# mcu.net
KiCad netlist of a schematic drawn in Altium Designer
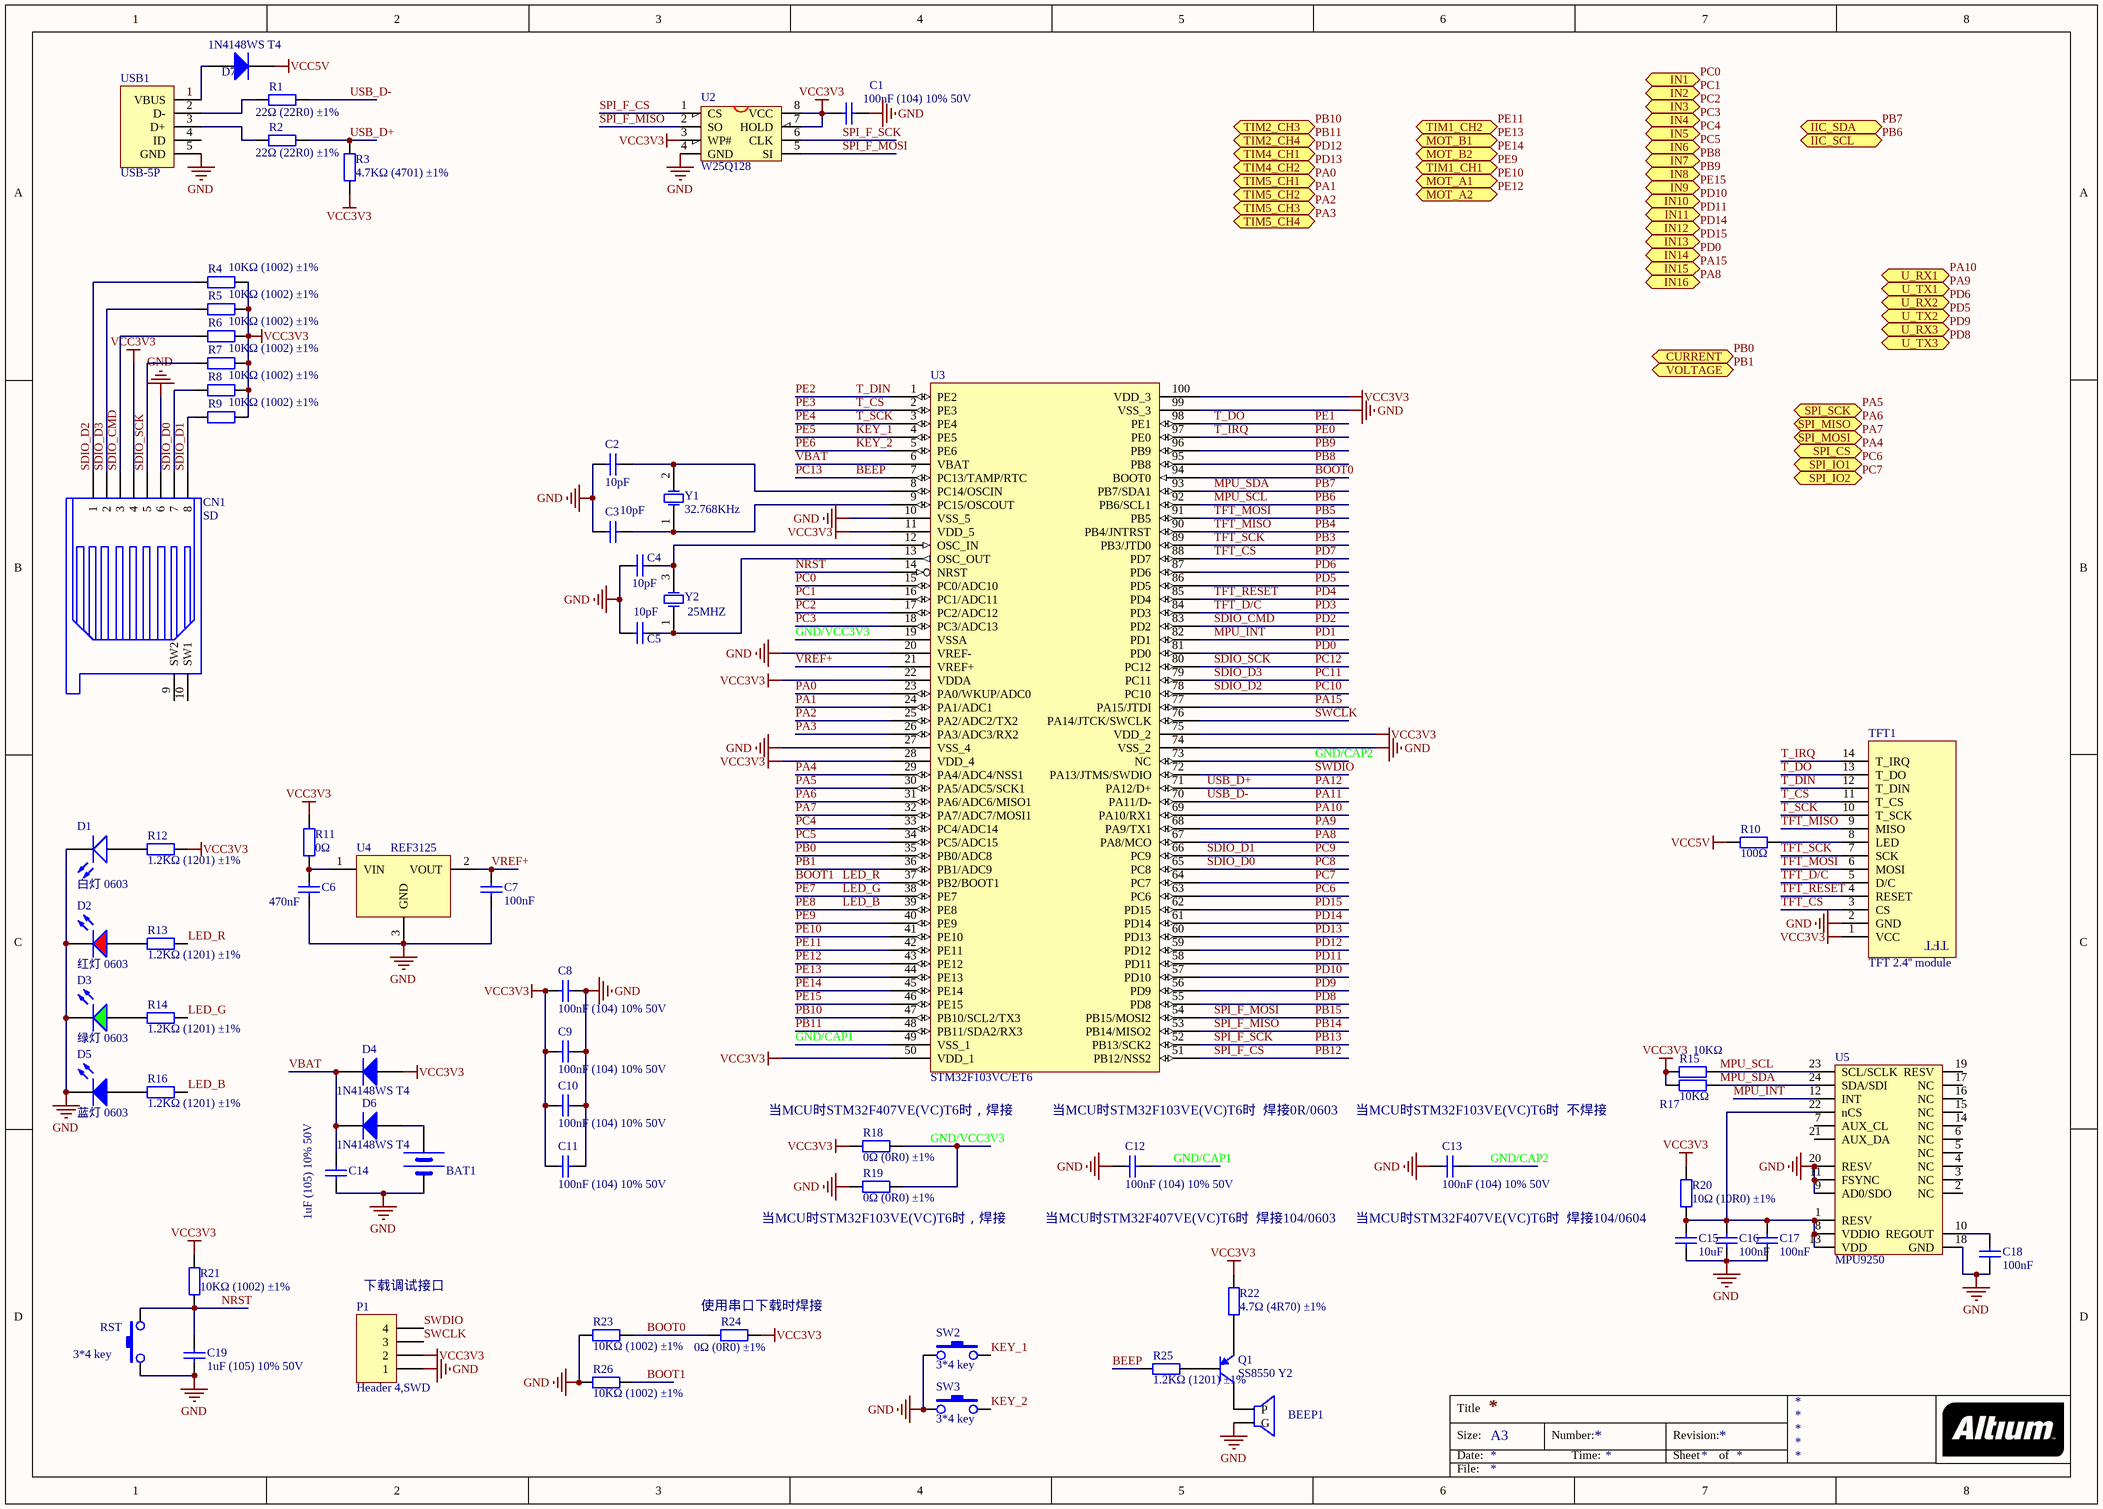
[diagram p0: mcu.SchDoc]

(export (version "E")
  (design (tool "Eeschema 10.0.6"))
  (components
    (comp (ref "BAT1") (value "BATT") (footprint "BATM") (libsource (lib "EXPLORER") (part "BAT")))
    (comp (ref "BEEP1") (value "BEEP") (footprint "BELL-5") (libsource (lib "EXPLORER") (part "BEEP")))
    (comp (ref "C1")
      (value "100nF (104) 10% 50V")
      (footprint "0603_C")
      (description "贴片电容")
      (libsource (lib "Cap") (part "0603 100nF (104) 10% 50V"))
    )
    (comp (ref "C2")
      (value "10pF")
      (footprint "0603_C")
      (description "贴片电容")
      (libsource (lib "Cap") (part "0603 10pF (100) 5% 50V"))
    )
    (comp (ref "C3")
      (value "10pF")
      (footprint "0603_C")
      (description "贴片电容")
      (libsource (lib "Cap") (part "0603 10pF (100) 5% 50V"))
    )
    (comp (ref "C4")
      (value "10pF")
      (footprint "0603_C")
      (description "贴片电容")
      (libsource (lib "Cap") (part "0603 10pF (100) 5% 50V"))
    )
    (comp (ref "C5")
      (value "10pF")
      (footprint "0603_C")
      (description "贴片电容")
      (libsource (lib "Cap") (part "0603 10pF (100) 5% 50V"))
    )
    (comp (ref "C6")
      (value "470nF")
      (footprint "0603_C")
      (description "贴片电容")
      (libsource (lib "Cap") (part "0603 470nF (474) 10% 25V"))
    )
    (comp (ref "C7")
      (value "100nF")
      (footprint "0603_C")
      (description "贴片电容")
      (libsource (lib "Cap") (part "0603 100nF (104) 10% 50V"))
    )
    (comp (ref "C8")
      (value "100nF (104) 10% 50V")
      (footprint "0603_C")
      (description "贴片电容")
      (libsource (lib "Cap") (part "0603 100nF (104) 10% 50V"))
    )
    (comp (ref "C9")
      (value "100nF (104) 10% 50V")
      (footprint "0603_C")
      (description "贴片电容")
      (libsource (lib "Cap") (part "0603 100nF (104) 10% 50V"))
    )
    (comp (ref "C10")
      (value "100nF (104) 10% 50V")
      (footprint "0603_C")
      (description "贴片电容")
      (libsource (lib "Cap") (part "0603 100nF (104) 10% 50V"))
    )
    (comp (ref "C11")
      (value "100nF (104) 10% 50V")
      (footprint "0603_C")
      (description "贴片电容")
      (libsource (lib "Cap") (part "0603 100nF (104) 10% 50V"))
    )
    (comp (ref "C12")
      (value "100nF (104) 10% 50V")
      (footprint "0603_C")
      (description "贴片电容")
      (libsource (lib "Cap") (part "0603 100nF (104) 10% 50V"))
    )
    (comp (ref "C13")
      (value "100nF (104) 10% 50V")
      (footprint "0603_C")
      (description "贴片电容")
      (libsource (lib "Cap") (part "0603 100nF (104) 10% 50V"))
    )
    (comp (ref "C14")
      (value "1uF (105) 10% 50V")
      (footprint "0603_C")
      (description "贴片电容")
      (libsource (lib "Cap") (part "0603 1uF (105) 10% 50V"))
    )
    (comp (ref "C15")
      (value "10uF")
      (footprint "0603_C")
      (description "贴片电容")
      (libsource (lib "Cap") (part "0603 10uF (106) 10% 10V"))
    )
    (comp (ref "C16")
      (value "100nF")
      (footprint "0603_C")
      (description "贴片电容")
      (libsource (lib "Cap") (part "0603 100nF (104) 10% 50V"))
    )
    (comp (ref "C17")
      (value "100nF")
      (footprint "0603_C")
      (description "贴片电容")
      (libsource (lib "Cap") (part "0603 100nF (104) 10% 50V"))
    )
    (comp (ref "C18")
      (value "100nF")
      (footprint "0603_C")
      (description "贴片电容")
      (libsource (lib "Cap") (part "0603 100nF (104) 10% 50V"))
    )
    (comp (ref "C19")
      (value "1uF (105) 10% 50V")
      (footprint "0603_C")
      (description "贴片电容")
      (libsource (lib "Cap") (part "0603 1uF (105) 10% 50V"))
    )
    (comp (ref "CN1")
      (value "SD")
      (footprint "TF")
      (libsource (lib "STM32F407VET6mini最小系统-原理图库") (part "SMS016AFA5E"))
    )
    (comp (ref "D1")
      (value "白灯 0603")
      (footprint "0603_LED_S1")
      (description "发光二极管")
      (libsource (lib "LED") (part "0603 白灯"))
    )
    (comp (ref "D2")
      (value "红灯 0603")
      (footprint "0603_LED_S1")
      (description "发光二极管")
      (libsource (lib "LED") (part "0603 红灯"))
    )
    (comp (ref "D3")
      (value "绿灯 0603")
      (footprint "0603_LED_S1")
      (description "发光二极管")
      (libsource (lib "LED") (part "0603 绿灯"))
    )
    (comp (ref "D4")
      (value "1N4148WS T4")
      (footprint "SOD-323")
      (description "二极管")
      (libsource (lib "Diode") (part "SOD-323 1N4148WS T4"))
    )
    (comp (ref "D5")
      (value "蓝灯 0603")
      (footprint "0603_LED_S1")
      (description "发光二极管")
      (libsource (lib "LED") (part "0603 蓝灯"))
    )
    (comp (ref "D6")
      (value "1N4148WS T4")
      (footprint "SOD-323")
      (description "二极管")
      (libsource (lib "Diode") (part "SOD-323 1N4148WS T4"))
    )
    (comp (ref "D7")
      (value "1N4148WS T4")
      (footprint "SOD-323")
      (description "二极管")
      (libsource (lib "Diode") (part "SOD-323 1N4148WS T4"))
    )
    (comp (ref "P1")
      (value "Header 4,SWD")
      (footprint "HDR1X4")
      (description "Header, 4-Pin")
      (fields (field (name "PUBLISHER") "Altium Limited"))
      (libsource (lib "Miscellaneous Connectors") (part "Header 4"))
    )
    (comp (ref "Q1")
      (value "SS8550 Y2")
      (footprint "SOT-23(SOT-23-3)")
      (description "三极管")
      (libsource (lib "Transistor_PNP") (part "SOT-23 SS8550 Y2"))
    )
    (comp (ref "R1")
      (value "22Ω (22R0) ±1%")
      (footprint "0603_R")
      (description "贴片电阻")
      (libsource (lib "RES") (part "0603 22Ω (22R0) 1%"))
    )
    (comp (ref "R2")
      (value "22Ω (22R0) ±1%")
      (footprint "0603_R")
      (description "贴片电阻")
      (libsource (lib "RES") (part "0603 22Ω (22R0) 1%"))
    )
    (comp (ref "R3")
      (value "4.7KΩ (4701) ±1%")
      (footprint "0603_R")
      (description "贴片电阻")
      (libsource (lib "RES") (part "0603 4.7KΩ (4701) 1%"))
    )
    (comp (ref "R4")
      (value "10KΩ (1002) ±1%")
      (footprint "0603_R")
      (description "贴片电阻")
      (libsource (lib "RES") (part "0603 10KΩ (1002) 1%"))
    )
    (comp (ref "R5")
      (value "10KΩ (1002) ±1%")
      (footprint "0603_R")
      (description "贴片电阻")
      (libsource (lib "RES") (part "0603 10KΩ (1002) 1%"))
    )
    (comp (ref "R6")
      (value "10KΩ (1002) ±1%")
      (footprint "0603_R")
      (description "贴片电阻")
      (libsource (lib "RES") (part "0603 10KΩ (1002) 1%"))
    )
    (comp (ref "R7")
      (value "10KΩ (1002) ±1%")
      (footprint "0603_R")
      (description "贴片电阻")
      (libsource (lib "RES") (part "0603 10KΩ (1002) 1%"))
    )
    (comp (ref "R8")
      (value "10KΩ (1002) ±1%")
      (footprint "0603_R")
      (description "贴片电阻")
      (libsource (lib "RES") (part "0603 10KΩ (1002) 1%"))
    )
    (comp (ref "R9")
      (value "10KΩ (1002) ±1%")
      (footprint "0603_R")
      (description "贴片电阻")
      (libsource (lib "RES") (part "0603 10KΩ (1002) 1%"))
    )
    (comp (ref "R10")
      (value "100Ω")
      (footprint "0603_R")
      (description "贴片电阻")
      (libsource (lib "RES") (part "0603 100Ω (1000) 1%"))
    )
    (comp (ref "R11")
      (value "0Ω")
      (footprint "0603_R")
      (description "贴片电阻")
      (libsource (lib "") (part "0603 0Ω (0R0) 1%_1"))
    )
    (comp (ref "R12")
      (value "1.2KΩ (1201) ±1%")
      (footprint "0603_R")
      (description "贴片电阻")
      (libsource (lib "RES") (part "0603 1.2KΩ (1201) 1%"))
    )
    (comp (ref "R13")
      (value "1.2KΩ (1201) ±1%")
      (footprint "0603_R")
      (description "贴片电阻")
      (libsource (lib "RES") (part "0603 1.2KΩ (1201) 1%"))
    )
    (comp (ref "R14")
      (value "1.2KΩ (1201) ±1%")
      (footprint "0603_R")
      (description "贴片电阻")
      (libsource (lib "RES") (part "0603 1.2KΩ (1201) 1%"))
    )
    (comp (ref "R15")
      (value "10KΩ")
      (footprint "0603_R")
      (description "贴片电阻")
      (libsource (lib "") (part "0603 10KΩ (1002) 1%_2"))
    )
    (comp (ref "R16")
      (value "1.2KΩ (1201) ±1%")
      (footprint "0603_R")
      (description "贴片电阻")
      (libsource (lib "RES") (part "0603 1.2KΩ (1201) 1%"))
    )
    (comp (ref "R17")
      (value "10KΩ")
      (footprint "0603_R")
      (description "贴片电阻")
      (libsource (lib "") (part "0603 10KΩ (1002) 1%_2"))
    )
    (comp (ref "R18")
      (value "0Ω (0R0) ±1%")
      (footprint "0603_R")
      (description "贴片电阻")
      (libsource (lib "RES") (part "0603 0Ω (0R0) 1%"))
    )
    (comp (ref "R19")
      (value "0Ω (0R0) ±1%")
      (footprint "0603_R")
      (description "贴片电阻")
      (libsource (lib "RES") (part "0603 0Ω (0R0) 1%"))
    )
    (comp (ref "R20")
      (value "10Ω (10R0) ±1%")
      (footprint "0603_R")
      (description "贴片电阻")
      (libsource (lib "RES") (part "0603 10Ω (10R0) 1%"))
    )
    (comp (ref "R21")
      (value "10KΩ (1002) ±1%")
      (footprint "0603_R")
      (description "贴片电阻")
      (libsource (lib "") (part "0603 10KΩ (1002) 1%_1"))
    )
    (comp (ref "R22")
      (value "4.7Ω (4R70) ±1%")
      (footprint "0603_R")
      (description "贴片电阻")
      (libsource (lib "RES") (part "0603 4.7Ω (4R70) 1%"))
    )
    (comp (ref "R23")
      (value "10KΩ (1002) ±1%")
      (footprint "0603_R")
      (description "贴片电阻")
      (libsource (lib "RES") (part "0603 10KΩ (1002) 1%"))
    )
    (comp (ref "R24")
      (value "0Ω (0R0) ±1%")
      (footprint "0603_R")
      (description "贴片电阻")
      (libsource (lib "RES") (part "0603 0Ω (0R0) 1%"))
    )
    (comp (ref "R25")
      (value "1.2KΩ (1201) ±1%")
      (footprint "0603_R")
      (description "贴片电阻")
      (libsource (lib "RES") (part "0603 1.2KΩ (1201) 1%"))
    )
    (comp (ref "R26")
      (value "10KΩ (1002) ±1%")
      (footprint "0603_R")
      (description "贴片电阻")
      (libsource (lib "RES") (part "0603 10KΩ (1002) 1%"))
    )
    (comp (ref "RST")
      (value "3*4 key")
      (footprint "KEY-SMT")
      (description "SWITCH")
      (libsource (lib "STM32F407VET6mini最小系统-原理图库") (part "SW-PB_V"))
    )
    (comp (ref "SW2")
      (value "3*4 key")
      (footprint "KEY-SMT")
      (description "SWITCH")
      (libsource (lib "STM32F407VET6mini最小系统-原理图库") (part "SW-PB_V"))
    )
    (comp (ref "SW3")
      (value "3*4 key")
      (footprint "KEY-SMT")
      (description "SWITCH")
      (libsource (lib "STM32F407VET6mini最小系统-原理图库") (part "SW-PB_V"))
    )
    (comp (ref "TFT1")
      (value "TFT 2.4'' module")
      (footprint "TFT 2.4'' module")
      (libsource (lib "MySchlib") (part "TFT 2.4'' module"))
    )
    (comp (ref "U2")
      (value "W25Q128")
      (footprint "SOIC-8")
      (description "W25X16;SST25VF016;MX25L1605")
      (libsource (lib "EXPLORER") (part "W25X16"))
    )
    (comp (ref "U3")
      (value "STM32F103VC/ET6")
      (footprint "LQFP-100")
      (libsource (lib "STM32F407VET6mini最小系统-原理图库") (part "STM32F103VBH6"))
    )
    (comp (ref "U4")
      (value "REF3125")
      (footprint "SOT-23(SOT-23-3)")
      (description "电压基准芯片")
      (libsource (lib "*") (part "REF3125"))
    )
    (comp (ref "U5")
      (value "MPU9250")
      (footprint "QFN24-t")
      (description "9轴运动处理传感器")
      (libsource (lib "STM32F429_F746") (part "MPU9250"))
    )
    (comp (ref "USB1")
      (value "USB-5P")
      (footprint "USB-MICRO_B")
      (description "微型USB母座")
      (libsource (lib "*") (part "USB-5P"))
    )
    (comp (ref "Y1")
      (value "32.768KHz")
      (footprint "MC-306")
      (description "Crystal Oscillator")
      (fields (field (name "PUBLISHER") "Altium Limited"))
      (libsource (lib "STM32F407VET6mini最小系统-原理图库") (part "XTAL"))
    )
    (comp (ref "Y2")
      (value "25MHZ")
      (footprint "SMD-3225_4P")
      (description "贴片晶振")
      (libsource (lib "CrystalOscillator") (part "SMD-3225_4P  25MHZ 12PF 10PPM"))
    )
  )
  (nets
    (net (code "1") (name "/BEEP") (class "Default")
      (node (ref "R25") (pin "1") (pinfunction "1_1") (pintype "passive"))
      (node (ref "U3") (pin "7") (pinfunction "PC13/TAMP/RTC_7") (pintype "bidirectional"))
    )
    (net (code "2") (name "/BOOT0") (class "Default")
      (node (ref "R23") (pin "1") (pinfunction "1_1") (pintype "passive"))
      (node (ref "R24") (pin "1") (pinfunction "1_1") (pintype "passive"))
      (node (ref "U3") (pin "94") (pinfunction "BOOT0_94") (pintype "input"))
    )
    (net (code "3") (name "/BOOT1") (class "Default")
      (node (ref "R13") (pin "2") (pinfunction "2_2") (pintype "passive"))
      (node (ref "R26") (pin "1") (pinfunction "1_1") (pintype "passive"))
      (node (ref "U3") (pin "37") (pinfunction "PB2/BOOT1_37") (pintype "bidirectional"))
    )
    (net (code "4") (name "/GND{slash}CAP1") (class "Default")
      (node (ref "C12") (pin "2") (pinfunction "2_2") (pintype "passive"))
      (node (ref "U3") (pin "49") (pinfunction "VSS_1_49") (pintype "power_in"))
    )
    (net (code "5") (name "/GND{slash}CAP2") (class "Default")
      (node (ref "C13") (pin "2") (pinfunction "2_2") (pintype "passive"))
      (node (ref "U3") (pin "73") (pinfunction "NC_73") (pintype "bidirectional"))
    )
    (net (code "6") (name "/GND{slash}VCC3V3") (class "Default")
      (node (ref "R18") (pin "2") (pinfunction "2_2") (pintype "passive"))
      (node (ref "R19") (pin "2") (pinfunction "2_2") (pintype "passive"))
      (node (ref "U3") (pin "19") (pinfunction "VSSA_19") (pintype "power_in"))
    )
    (net (code "7") (name "/KEY_1") (class "Default")
      (node (ref "SW2") (pin "2") (pinfunction "2_2") (pintype "passive"))
      (node (ref "U3") (pin "4") (pinfunction "PE5_4") (pintype "bidirectional"))
    )
    (net (code "8") (name "/KEY_2") (class "Default")
      (node (ref "SW3") (pin "2") (pinfunction "2_2") (pintype "passive"))
      (node (ref "U3") (pin "5") (pinfunction "PE6_5") (pintype "bidirectional"))
    )
    (net (code "9") (name "/LED_B") (class "Default")
      (node (ref "R16") (pin "2") (pinfunction "2_2") (pintype "passive"))
      (node (ref "U3") (pin "39") (pinfunction "PE8_39") (pintype "bidirectional"))
    )
    (net (code "10") (name "/LED_G") (class "Default")
      (node (ref "R14") (pin "2") (pinfunction "2_2") (pintype "passive"))
      (node (ref "U3") (pin "38") (pinfunction "PE7_38") (pintype "bidirectional"))
    )
    (net (code "11") (name "/MPU_INT") (class "Default")
      (node (ref "U3") (pin "82") (pinfunction "PD1_82") (pintype "bidirectional"))
      (node (ref "U5") (pin "12") (pinfunction "INT_12") (pintype "passive"))
    )
    (net (code "12") (name "/MPU_SCL") (class "Default")
      (node (ref "R15") (pin "2") (pinfunction "2_2") (pintype "passive"))
      (node (ref "U3") (pin "92") (pinfunction "PB6/SCL1_92") (pintype "bidirectional"))
      (node (ref "U5") (pin "23") (pinfunction "SCL/SCLK_23") (pintype "passive"))
    )
    (net (code "13") (name "/MPU_SDA") (class "Default")
      (node (ref "R17") (pin "2") (pinfunction "2_2") (pintype "passive"))
      (node (ref "U3") (pin "93") (pinfunction "PB7/SDA1_93") (pintype "bidirectional"))
      (node (ref "U5") (pin "24") (pinfunction "SDA/SDI_24") (pintype "passive"))
    )
    (net (code "14") (name "/NRST") (class "Default")
      (node (ref "C19") (pin "2") (pinfunction "2_2") (pintype "passive"))
      (node (ref "R21") (pin "1") (pinfunction "1_1") (pintype "passive"))
      (node (ref "RST") (pin "2") (pinfunction "2_2") (pintype "passive"))
      (node (ref "U3") (pin "14") (pinfunction "NRST_14") (pintype "input"))
    )
    (net (code "15") (name "/PA0") (class "Default")
      (node (ref "U3") (pin "23") (pinfunction "PA0/WKUP/ADC0_23") (pintype "bidirectional"))
    )
    (net (code "16") (name "/PA1") (class "Default")
      (node (ref "U3") (pin "24") (pinfunction "PA1/ADC1_24") (pintype "bidirectional"))
    )
    (net (code "17") (name "/PA2") (class "Default")
      (node (ref "U3") (pin "25") (pinfunction "PA2/ADC2/TX2_25") (pintype "bidirectional"))
    )
    (net (code "18") (name "/PA3") (class "Default")
      (node (ref "U3") (pin "26") (pinfunction "PA3/ADC3/RX2_26") (pintype "bidirectional"))
    )
    (net (code "19") (name "/PA4") (class "Default")
      (node (ref "U3") (pin "29") (pinfunction "PA4/ADC4/NSS1_29") (pintype "bidirectional"))
    )
    (net (code "20") (name "/PA5") (class "Default")
      (node (ref "U3") (pin "30") (pinfunction "PA5/ADC5/SCK1_30") (pintype "bidirectional"))
    )
    (net (code "21") (name "/PA6") (class "Default")
      (node (ref "U3") (pin "31") (pinfunction "PA6/ADC6/MISO1_31") (pintype "bidirectional"))
    )
    (net (code "22") (name "/PA7") (class "Default")
      (node (ref "U3") (pin "32") (pinfunction "PA7/ADC7/MOSI1_32") (pintype "bidirectional"))
    )
    (net (code "23") (name "/PA8") (class "Default")
      (node (ref "U3") (pin "67") (pinfunction "PA8/MCO_67") (pintype "bidirectional"))
    )
    (net (code "24") (name "/PA9") (class "Default")
      (node (ref "U3") (pin "68") (pinfunction "PA9/TX1_68") (pintype "bidirectional"))
    )
    (net (code "25") (name "/PA10") (class "Default")
      (node (ref "U3") (pin "69") (pinfunction "PA10/RX1_69") (pintype "bidirectional"))
    )
    (net (code "26") (name "/PA11") (class "Default")
      (node (ref "R1") (pin "2") (pinfunction "2_2") (pintype "passive"))
      (node (ref "U3") (pin "70") (pinfunction "PA11/D-_70") (pintype "bidirectional"))
    )
    (net (code "27") (name "/PA12") (class "Default")
      (node (ref "R2") (pin "2") (pinfunction "2_2") (pintype "passive"))
      (node (ref "R3") (pin "2") (pinfunction "2_2") (pintype "passive"))
      (node (ref "U3") (pin "71") (pinfunction "PA12/D+_71") (pintype "bidirectional"))
    )
    (net (code "28") (name "/PA15") (class "Default")
      (node (ref "U3") (pin "77") (pinfunction "PA15/JTDI_77") (pintype "bidirectional"))
    )
    (net (code "29") (name "/PB0") (class "Default")
      (node (ref "U3") (pin "35") (pinfunction "PB0/ADC8_35") (pintype "bidirectional"))
    )
    (net (code "30") (name "/PB1") (class "Default")
      (node (ref "U3") (pin "36") (pinfunction "PB1/ADC9_36") (pintype "bidirectional"))
    )
    (net (code "31") (name "/PB3") (class "Default")
      (node (ref "TFT1") (pin "7") (pinfunction "SCK_7") (pintype "passive"))
      (node (ref "U3") (pin "89") (pinfunction "PB3/JTD0_89") (pintype "bidirectional"))
    )
    (net (code "32") (name "/PB4") (class "Default")
      (node (ref "TFT1") (pin "9") (pinfunction "MISO_9") (pintype "passive"))
      (node (ref "U3") (pin "90") (pinfunction "PB4/JNTRST_90") (pintype "bidirectional"))
    )
    (net (code "33") (name "/PB5") (class "Default")
      (node (ref "TFT1") (pin "6") (pinfunction "MOSI_6") (pintype "passive"))
      (node (ref "U3") (pin "91") (pinfunction "PB5_91") (pintype "bidirectional"))
    )
    (net (code "34") (name "/PB8") (class "Default")
      (node (ref "U3") (pin "95") (pinfunction "PB8_95") (pintype "bidirectional"))
    )
    (net (code "35") (name "/PB9") (class "Default")
      (node (ref "U3") (pin "96") (pinfunction "PB9_96") (pintype "bidirectional"))
    )
    (net (code "36") (name "/PB10") (class "Default")
      (node (ref "U3") (pin "47") (pinfunction "PB10/SCL2/TX3_47") (pintype "bidirectional"))
    )
    (net (code "37") (name "/PB11") (class "Default")
      (node (ref "U3") (pin "48") (pinfunction "PB11/SDA2/RX3_48") (pintype "bidirectional"))
    )
    (net (code "38") (name "/PB12") (class "Default")
      (node (ref "U2") (pin "1") (pinfunction "CS_1") (pintype "passive"))
      (node (ref "U3") (pin "51") (pinfunction "PB12/NSS2_51") (pintype "bidirectional"))
    )
    (net (code "39") (name "/PB13") (class "Default")
      (node (ref "U2") (pin "6") (pinfunction "CLK_6") (pintype "passive"))
      (node (ref "U3") (pin "52") (pinfunction "PB13/SCK2_52") (pintype "bidirectional"))
    )
    (net (code "40") (name "/PB14") (class "Default")
      (node (ref "U2") (pin "2") (pinfunction "SO_2") (pintype "passive"))
      (node (ref "U3") (pin "53") (pinfunction "PB14/MISO2_53") (pintype "bidirectional"))
    )
    (net (code "41") (name "/PB15") (class "Default")
      (node (ref "U2") (pin "5") (pinfunction "SI_5") (pintype "passive"))
      (node (ref "U3") (pin "54") (pinfunction "PB15/MOSI2_54") (pintype "bidirectional"))
    )
    (net (code "42") (name "/PC0") (class "Default")
      (node (ref "U3") (pin "15") (pinfunction "PC0/ADC10_15") (pintype "bidirectional"))
    )
    (net (code "43") (name "/PC1") (class "Default")
      (node (ref "U3") (pin "16") (pinfunction "PC1/ADC11_16") (pintype "bidirectional"))
    )
    (net (code "44") (name "/PC2") (class "Default")
      (node (ref "U3") (pin "17") (pinfunction "PC2/ADC12_17") (pintype "bidirectional"))
    )
    (net (code "45") (name "/PC3") (class "Default")
      (node (ref "U3") (pin "18") (pinfunction "PC3/ADC13_18") (pintype "bidirectional"))
    )
    (net (code "46") (name "/PC4") (class "Default")
      (node (ref "U3") (pin "33") (pinfunction "PC4/ADC14_33") (pintype "bidirectional"))
    )
    (net (code "47") (name "/PC5") (class "Default")
      (node (ref "U3") (pin "34") (pinfunction "PC5/ADC15_34") (pintype "bidirectional"))
    )
    (net (code "48") (name "/PC6") (class "Default")
      (node (ref "U3") (pin "63") (pinfunction "PC6_63") (pintype "bidirectional"))
    )
    (net (code "49") (name "/PC7") (class "Default")
      (node (ref "U3") (pin "64") (pinfunction "PC7_64") (pintype "bidirectional"))
    )
    (net (code "50") (name "/PC8") (class "Default")
      (node (ref "CN1") (pin "7") (pinfunction "7_7") (pintype "passive"))
      (node (ref "R8") (pin "2") (pinfunction "2_2") (pintype "passive"))
      (node (ref "U3") (pin "65") (pinfunction "PC8_65") (pintype "bidirectional"))
    )
    (net (code "51") (name "/PC9") (class "Default")
      (node (ref "CN1") (pin "8") (pinfunction "8_8") (pintype "passive"))
      (node (ref "R9") (pin "2") (pinfunction "2_2") (pintype "passive"))
      (node (ref "U3") (pin "66") (pinfunction "PC9_66") (pintype "bidirectional"))
    )
    (net (code "52") (name "/PC10") (class "Default")
      (node (ref "CN1") (pin "1") (pinfunction "1_1") (pintype "passive"))
      (node (ref "R4") (pin "2") (pinfunction "2_2") (pintype "passive"))
      (node (ref "U3") (pin "78") (pinfunction "PC10_78") (pintype "bidirectional"))
    )
    (net (code "53") (name "/PC11") (class "Default")
      (node (ref "CN1") (pin "2") (pinfunction "2_2") (pintype "passive"))
      (node (ref "R5") (pin "2") (pinfunction "2_2") (pintype "passive"))
      (node (ref "U3") (pin "79") (pinfunction "PC11_79") (pintype "bidirectional"))
    )
    (net (code "54") (name "/PC12") (class "Default")
      (node (ref "CN1") (pin "5") (pinfunction "5_5") (pintype "passive"))
      (node (ref "R7") (pin "2") (pinfunction "2_2") (pintype "passive"))
      (node (ref "U3") (pin "80") (pinfunction "PC12_80") (pintype "bidirectional"))
    )
    (net (code "55") (name "/PD0") (class "Default")
      (node (ref "U3") (pin "81") (pinfunction "PD0_81") (pintype "bidirectional"))
    )
    (net (code "56") (name "/PD2") (class "Default")
      (node (ref "CN1") (pin "3") (pinfunction "3_3") (pintype "passive"))
      (node (ref "R6") (pin "2") (pinfunction "2_2") (pintype "passive"))
      (node (ref "U3") (pin "83") (pinfunction "PD2_83") (pintype "bidirectional"))
    )
    (net (code "57") (name "/PD3") (class "Default")
      (node (ref "TFT1") (pin "5") (pinfunction "D/C_5") (pintype "passive"))
      (node (ref "U3") (pin "84") (pinfunction "PD3_84") (pintype "bidirectional"))
    )
    (net (code "58") (name "/PD4") (class "Default")
      (node (ref "TFT1") (pin "4") (pinfunction "RESET_4") (pintype "passive"))
      (node (ref "U3") (pin "85") (pinfunction "PD4_85") (pintype "bidirectional"))
    )
    (net (code "59") (name "/PD5") (class "Default")
      (node (ref "U3") (pin "86") (pinfunction "PD5_86") (pintype "bidirectional"))
    )
    (net (code "60") (name "/PD6") (class "Default")
      (node (ref "U3") (pin "87") (pinfunction "PD6_87") (pintype "bidirectional"))
    )
    (net (code "61") (name "/PD7") (class "Default")
      (node (ref "TFT1") (pin "3") (pinfunction "CS_3") (pintype "passive"))
      (node (ref "U3") (pin "88") (pinfunction "PD7_88") (pintype "bidirectional"))
    )
    (net (code "62") (name "/PD8") (class "Default")
      (node (ref "U3") (pin "55") (pinfunction "PD8_55") (pintype "bidirectional"))
    )
    (net (code "63") (name "/PD9") (class "Default")
      (node (ref "U3") (pin "56") (pinfunction "PD9_56") (pintype "bidirectional"))
    )
    (net (code "64") (name "/PD10") (class "Default")
      (node (ref "U3") (pin "57") (pinfunction "PD10_57") (pintype "bidirectional"))
    )
    (net (code "65") (name "/PD11") (class "Default")
      (node (ref "U3") (pin "58") (pinfunction "PD11_58") (pintype "bidirectional"))
    )
    (net (code "66") (name "/PD12") (class "Default")
      (node (ref "U3") (pin "59") (pinfunction "PD12_59") (pintype "bidirectional"))
    )
    (net (code "67") (name "/PD13") (class "Default")
      (node (ref "U3") (pin "60") (pinfunction "PD13_60") (pintype "bidirectional"))
    )
    (net (code "68") (name "/PD14") (class "Default")
      (node (ref "U3") (pin "61") (pinfunction "PD14_61") (pintype "bidirectional"))
    )
    (net (code "69") (name "/PD15") (class "Default")
      (node (ref "U3") (pin "62") (pinfunction "PD15_62") (pintype "bidirectional"))
    )
    (net (code "70") (name "/PE0") (class "Default")
      (node (ref "TFT1") (pin "14") (pinfunction "T_IRQ_14") (pintype "passive"))
      (node (ref "U3") (pin "97") (pinfunction "PE0_97") (pintype "bidirectional"))
    )
    (net (code "71") (name "/PE1") (class "Default")
      (node (ref "TFT1") (pin "13") (pinfunction "T_DO_13") (pintype "passive"))
      (node (ref "U3") (pin "98") (pinfunction "PE1_98") (pintype "bidirectional"))
    )
    (net (code "72") (name "/PE2") (class "Default")
      (node (ref "TFT1") (pin "12") (pinfunction "T_DIN_12") (pintype "passive"))
      (node (ref "U3") (pin "1") (pinfunction "PE2_1") (pintype "bidirectional"))
    )
    (net (code "73") (name "/PE3") (class "Default")
      (node (ref "TFT1") (pin "11") (pinfunction "T_CS_11") (pintype "passive"))
      (node (ref "U3") (pin "2") (pinfunction "PE3_2") (pintype "bidirectional"))
    )
    (net (code "74") (name "/PE4") (class "Default")
      (node (ref "TFT1") (pin "10") (pinfunction "T_SCK_10") (pintype "passive"))
      (node (ref "U3") (pin "3") (pinfunction "PE4_3") (pintype "bidirectional"))
    )
    (net (code "75") (name "/PE9") (class "Default")
      (node (ref "U3") (pin "40") (pinfunction "PE9_40") (pintype "bidirectional"))
    )
    (net (code "76") (name "/PE10") (class "Default")
      (node (ref "U3") (pin "41") (pinfunction "PE10_41") (pintype "bidirectional"))
    )
    (net (code "77") (name "/PE11") (class "Default")
      (node (ref "U3") (pin "42") (pinfunction "PE11_42") (pintype "bidirectional"))
    )
    (net (code "78") (name "/PE12") (class "Default")
      (node (ref "U3") (pin "43") (pinfunction "PE12_43") (pintype "bidirectional"))
    )
    (net (code "79") (name "/PE13") (class "Default")
      (node (ref "U3") (pin "44") (pinfunction "PE13_44") (pintype "bidirectional"))
    )
    (net (code "80") (name "/PE14") (class "Default")
      (node (ref "U3") (pin "45") (pinfunction "PE14_45") (pintype "bidirectional"))
    )
    (net (code "81") (name "/PE15") (class "Default")
      (node (ref "U3") (pin "46") (pinfunction "PE15_46") (pintype "bidirectional"))
    )
    (net (code "82") (name "/SWCLK") (class "Default")
      (node (ref "P1") (pin "3") (pinfunction "3_3") (pintype "passive"))
      (node (ref "U3") (pin "76") (pinfunction "PA14/JTCK/SWCLK_76") (pintype "bidirectional"))
    )
    (net (code "83") (name "/SWDIO") (class "Default")
      (node (ref "P1") (pin "4") (pinfunction "4_4") (pintype "passive"))
      (node (ref "U3") (pin "72") (pinfunction "PA13/JTMS/SWDIO_72") (pintype "bidirectional"))
    )
    (net (code "84") (name "/VBAT") (class "Default")
      (node (ref "C14") (pin "2") (pinfunction "2_2") (pintype "passive"))
      (node (ref "D4") (pin "2") (pinfunction "K_2") (pintype "passive"))
      (node (ref "D6") (pin "2") (pinfunction "K_2") (pintype "passive"))
      (node (ref "U3") (pin "6") (pinfunction "VBAT_6") (pintype "power_in"))
    )
    (net (code "85") (name "/VREF+") (class "Default")
      (node (ref "C7") (pin "2") (pinfunction "2_2") (pintype "passive"))
      (node (ref "U3") (pin "21") (pinfunction "VREF+_21") (pintype "power_in"))
      (node (ref "U4") (pin "2") (pinfunction "VOUT_2") (pintype "passive"))
    )
    (net (code "86") (name "GND") (class "Default")
      (node (ref "BAT1") (pin "2") (pinfunction "GND_2") (pintype "passive"))
      (node (ref "BEEP1") (pin "2") (pinfunction "G_2") (pintype "passive"))
      (node (ref "C1") (pin "2") (pinfunction "2_2") (pintype "passive"))
      (node (ref "C10") (pin "2") (pinfunction "2_2") (pintype "passive"))
      (node (ref "C11") (pin "2") (pinfunction "2_2") (pintype "passive"))
      (node (ref "C12") (pin "1") (pinfunction "1_1") (pintype "passive"))
      (node (ref "C13") (pin "1") (pinfunction "1_1") (pintype "passive"))
      (node (ref "C14") (pin "1") (pinfunction "1_1") (pintype "passive"))
      (node (ref "C15") (pin "1") (pinfunction "1_1") (pintype "passive"))
      (node (ref "C16") (pin "1") (pinfunction "1_1") (pintype "passive"))
      (node (ref "C17") (pin "1") (pinfunction "1_1") (pintype "passive"))
      (node (ref "C18") (pin "1") (pinfunction "1_1") (pintype "passive"))
      (node (ref "C19") (pin "1") (pinfunction "1_1") (pintype "passive"))
      (node (ref "C2") (pin "1") (pinfunction "1_1") (pintype "passive"))
      (node (ref "C3") (pin "1") (pinfunction "1_1") (pintype "passive"))
      (node (ref "C4") (pin "1") (pinfunction "1_1") (pintype "passive"))
      (node (ref "C5") (pin "1") (pinfunction "1_1") (pintype "passive"))
      (node (ref "C6") (pin "1") (pinfunction "1_1") (pintype "passive"))
      (node (ref "C7") (pin "1") (pinfunction "1_1") (pintype "passive"))
      (node (ref "C8") (pin "2") (pinfunction "2_2") (pintype "passive"))
      (node (ref "C9") (pin "2") (pinfunction "2_2") (pintype "passive"))
      (node (ref "CN1") (pin "6") (pinfunction "6_6") (pintype "passive"))
      (node (ref "D1") (pin "K") (pinfunction "K_K") (pintype "passive"))
      (node (ref "D2") (pin "K") (pinfunction "K_K") (pintype "passive"))
      (node (ref "D3") (pin "K") (pinfunction "K_K") (pintype "passive"))
      (node (ref "D5") (pin "K") (pinfunction "K_K") (pintype "passive"))
      (node (ref "P1") (pin "1") (pinfunction "1_1") (pintype "passive"))
      (node (ref "R19") (pin "1") (pinfunction "1_1") (pintype "passive"))
      (node (ref "R23") (pin "2") (pinfunction "2_2") (pintype "passive"))
      (node (ref "R26") (pin "2") (pinfunction "2_2") (pintype "passive"))
      (node (ref "RST") (pin "1") (pinfunction "1_1") (pintype "passive"))
      (node (ref "SW2") (pin "1") (pinfunction "1_1") (pintype "passive"))
      (node (ref "SW3") (pin "1") (pinfunction "1_1") (pintype "passive"))
      (node (ref "TFT1") (pin "2") (pinfunction "GND_2") (pintype "passive"))
      (node (ref "U2") (pin "4") (pinfunction "GND_4") (pintype "passive"))
      (node (ref "U3") (pin "10") (pinfunction "VSS_5_10") (pintype "power_in"))
      (node (ref "U3") (pin "20") (pinfunction "VREF-_20") (pintype "power_in"))
      (node (ref "U3") (pin "27") (pinfunction "VSS_4_27") (pintype "power_in"))
      (node (ref "U3") (pin "74") (pinfunction "VSS_2_74") (pintype "power_in"))
      (node (ref "U3") (pin "99") (pinfunction "VSS_3_99") (pintype "power_in"))
      (node (ref "U4") (pin "3") (pinfunction "GND_3") (pintype "passive"))
      (node (ref "U5") (pin "11") (pinfunction "FSYNC_11") (pintype "passive"))
      (node (ref "U5") (pin "18") (pinfunction "GND_18") (pintype "passive"))
      (node (ref "U5") (pin "20") (pinfunction "RESV_20") (pintype "passive"))
      (node (ref "U5") (pin "9") (pinfunction "AD0/SDO_9") (pintype "passive"))
      (node (ref "USB1") (pin "5") (pinfunction "GND_5") (pintype "passive"))
    )
    (net (code "87") (name "Net-(BAT1-VCC)") (class "Default")
      (node (ref "BAT1") (pin "1") (pinfunction "VCC_1") (pintype "passive"))
      (node (ref "D6") (pin "1") (pinfunction "A_1") (pintype "passive"))
    )
    (net (code "88") (name "Net-(BEEP1-P)") (class "Default")
      (node (ref "BEEP1") (pin "1") (pinfunction "P_1") (pintype "passive"))
      (node (ref "Q1") (pin "3") (pinfunction "C_3") (pintype "passive"))
    )
    (net (code "89") (name "Net-(D1-PadA)") (class "Default")
      (node (ref "D1") (pin "A") (pinfunction "A_A") (pintype "passive"))
      (node (ref "R12") (pin "1") (pinfunction "1_1") (pintype "passive"))
    )
    (net (code "90") (name "Net-(D2-PadA)") (class "Default")
      (node (ref "D2") (pin "A") (pinfunction "A_A") (pintype "passive"))
      (node (ref "R13") (pin "1") (pinfunction "1_1") (pintype "passive"))
    )
    (net (code "91") (name "Net-(D3-PadA)") (class "Default")
      (node (ref "D3") (pin "A") (pinfunction "A_A") (pintype "passive"))
      (node (ref "R14") (pin "1") (pinfunction "1_1") (pintype "passive"))
    )
    (net (code "92") (name "Net-(D5-PadA)") (class "Default")
      (node (ref "D5") (pin "A") (pinfunction "A_A") (pintype "passive"))
      (node (ref "R16") (pin "1") (pinfunction "1_1") (pintype "passive"))
    )
    (net (code "93") (name "Net-(D7-A)") (class "Default")
      (node (ref "D7") (pin "1") (pinfunction "A_1") (pintype "passive"))
      (node (ref "USB1") (pin "1") (pinfunction "VBUS_1") (pintype "passive"))
    )
    (net (code "94") (name "Net-(Q1-B)") (class "Default")
      (node (ref "Q1") (pin "1") (pinfunction "B_1") (pintype "passive"))
      (node (ref "R25") (pin "2") (pinfunction "2_2") (pintype "passive"))
    )
    (net (code "95") (name "Net-(Q1-E)") (class "Default")
      (node (ref "Q1") (pin "2") (pinfunction "E_2") (pintype "passive"))
      (node (ref "R22") (pin "1") (pinfunction "1_1") (pintype "passive"))
    )
    (net (code "96") (name "Net-(TFT1-LED)") (class "Default")
      (node (ref "R10") (pin "2") (pinfunction "2_2") (pintype "passive"))
      (node (ref "TFT1") (pin "8") (pinfunction "LED_8") (pintype "passive"))
    )
    (net (code "97") (name "Net-(U3-OSC_IN)") (class "Default")
      (node (ref "C4") (pin "2") (pinfunction "2_2") (pintype "passive"))
      (node (ref "U3") (pin "12") (pinfunction "OSC_IN_12") (pintype "input"))
      (node (ref "Y2") (pin "3") (pinfunction "OSC2_3") (pintype "passive"))
    )
    (net (code "98") (name "Net-(U3-OSC_OUT)") (class "Default")
      (node (ref "C5") (pin "2") (pinfunction "2_2") (pintype "passive"))
      (node (ref "U3") (pin "13") (pinfunction "OSC_OUT_13") (pintype "output"))
      (node (ref "Y2") (pin "1") (pinfunction "OSC1_1") (pintype "passive"))
    )
    (net (code "99") (name "Net-(U3-PC14{slash}OSCIN)") (class "Default")
      (node (ref "C2") (pin "2") (pinfunction "2_2") (pintype "passive"))
      (node (ref "U3") (pin "8") (pinfunction "PC14/OSCIN_8") (pintype "bidirectional"))
      (node (ref "Y1") (pin "2") (pinfunction "OSC2_2") (pintype "passive"))
    )
    (net (code "100") (name "Net-(U3-PC15{slash}OSCOUT)") (class "Default")
      (node (ref "C3") (pin "2") (pinfunction "2_2") (pintype "passive"))
      (node (ref "U3") (pin "9") (pinfunction "PC15/OSCOUT_9") (pintype "bidirectional"))
      (node (ref "Y1") (pin "1") (pinfunction "OSC1_1") (pintype "passive"))
    )
    (net (code "101") (name "Net-(U4-VIN)") (class "Default")
      (node (ref "C6") (pin "2") (pinfunction "2_2") (pintype "passive"))
      (node (ref "R11") (pin "2") (pinfunction "2_2") (pintype "passive"))
      (node (ref "U4") (pin "1") (pinfunction "VIN_1") (pintype "passive"))
    )
    (net (code "102") (name "Net-(U5-REGOUT)") (class "Default")
      (node (ref "C18") (pin "2") (pinfunction "2_2") (pintype "passive"))
      (node (ref "U5") (pin "10") (pinfunction "REGOUT_10") (pintype "passive"))
    )
    (net (code "103") (name "Net-(U5-VDD)") (class "Default")
      (node (ref "C15") (pin "2") (pinfunction "2_2") (pintype "passive"))
      (node (ref "C16") (pin "2") (pinfunction "2_2") (pintype "passive"))
      (node (ref "C17") (pin "2") (pinfunction "2_2") (pintype "passive"))
      (node (ref "R20") (pin "1") (pinfunction "1_1") (pintype "passive"))
      (node (ref "U5") (pin "1") (pinfunction "RESV_1") (pintype "passive"))
      (node (ref "U5") (pin "13") (pinfunction "VDD_13") (pintype "passive"))
      (node (ref "U5") (pin "22") (pinfunction "nCS_22") (pintype "passive"))
      (node (ref "U5") (pin "8") (pinfunction "VDDIO_8") (pintype "passive"))
    )
    (net (code "104") (name "Net-(USB1-D+)") (class "Default")
      (node (ref "R2") (pin "1") (pinfunction "1_1") (pintype "passive"))
      (node (ref "USB1") (pin "3") (pinfunction "D+_3") (pintype "passive"))
    )
    (net (code "105") (name "Net-(USB1-D-)") (class "Default")
      (node (ref "R1") (pin "1") (pinfunction "1_1") (pintype "passive"))
      (node (ref "USB1") (pin "2") (pinfunction "D-_2") (pintype "passive"))
    )
    (net (code "106") (name "VCC3V3") (class "Default")
      (node (ref "C1") (pin "1") (pinfunction "1_1") (pintype "passive"))
      (node (ref "C10") (pin "1") (pinfunction "1_1") (pintype "passive"))
      (node (ref "C11") (pin "1") (pinfunction "1_1") (pintype "passive"))
      (node (ref "C8") (pin "1") (pinfunction "1_1") (pintype "passive"))
      (node (ref "C9") (pin "1") (pinfunction "1_1") (pintype "passive"))
      (node (ref "CN1") (pin "4") (pinfunction "4_4") (pintype "passive"))
      (node (ref "D4") (pin "1") (pinfunction "A_1") (pintype "passive"))
      (node (ref "P1") (pin "2") (pinfunction "2_2") (pintype "passive"))
      (node (ref "R11") (pin "1") (pinfunction "1_1") (pintype "passive"))
      (node (ref "R12") (pin "2") (pinfunction "2_2") (pintype "passive"))
      (node (ref "R15") (pin "1") (pinfunction "1_1") (pintype "passive"))
      (node (ref "R17") (pin "1") (pinfunction "1_1") (pintype "passive"))
      (node (ref "R18") (pin "1") (pinfunction "1_1") (pintype "passive"))
      (node (ref "R20") (pin "2") (pinfunction "2_2") (pintype "passive"))
      (node (ref "R21") (pin "2") (pinfunction "2_2") (pintype "passive"))
      (node (ref "R22") (pin "2") (pinfunction "2_2") (pintype "passive"))
      (node (ref "R24") (pin "2") (pinfunction "2_2") (pintype "passive"))
      (node (ref "R3") (pin "1") (pinfunction "1_1") (pintype "passive"))
      (node (ref "R4") (pin "1") (pinfunction "1_1") (pintype "passive"))
      (node (ref "R5") (pin "1") (pinfunction "1_1") (pintype "passive"))
      (node (ref "R6") (pin "1") (pinfunction "1_1") (pintype "passive"))
      (node (ref "R7") (pin "1") (pinfunction "1_1") (pintype "passive"))
      (node (ref "R8") (pin "1") (pinfunction "1_1") (pintype "passive"))
      (node (ref "R9") (pin "1") (pinfunction "1_1") (pintype "passive"))
      (node (ref "TFT1") (pin "1") (pinfunction "VCC_1") (pintype "passive"))
      (node (ref "U2") (pin "3") (pinfunction "WP#_3") (pintype "passive"))
      (node (ref "U2") (pin "7") (pinfunction "HOLD_7") (pintype "passive"))
      (node (ref "U2") (pin "8") (pinfunction "VCC_8") (pintype "passive"))
      (node (ref "U3") (pin "100") (pinfunction "VDD_3_100") (pintype "power_in"))
      (node (ref "U3") (pin "11") (pinfunction "VDD_5_11") (pintype "power_in"))
      (node (ref "U3") (pin "22") (pinfunction "VDDA_22") (pintype "power_in"))
      (node (ref "U3") (pin "28") (pinfunction "VDD_4_28") (pintype "power_in"))
      (node (ref "U3") (pin "50") (pinfunction "VDD_1_50") (pintype "power_in"))
      (node (ref "U3") (pin "75") (pinfunction "VDD_2_75") (pintype "power_in"))
    )
    (net (code "107") (name "VCC5V") (class "Default")
      (node (ref "D7") (pin "2") (pinfunction "K_2") (pintype "passive"))
      (node (ref "R10") (pin "1") (pinfunction "1_1") (pintype "passive"))
    )
    (net (code "108") (name "unconnected-(CN1-SW1-Pad10)") (class "Default")
      (node (ref "CN1") (pin "10") (pinfunction "SW1_10") (pintype "passive"))
    )
    (net (code "109") (name "unconnected-(CN1-SW2-Pad9)") (class "Default")
      (node (ref "CN1") (pin "9") (pinfunction "SW2_9") (pintype "passive"))
    )
    (net (code "110") (name "unconnected-(U5-AUX_CL-Pad7)") (class "Default")
      (node (ref "U5") (pin "7") (pinfunction "AUX_CL_7") (pintype "passive"))
    )
    (net (code "111") (name "unconnected-(U5-AUX_DA-Pad21)") (class "Default")
      (node (ref "U5") (pin "21") (pinfunction "AUX_DA_21") (pintype "passive"))
    )
    (net (code "112") (name "unconnected-(U5-NC-Pad2)") (class "Default")
      (node (ref "U5") (pin "2") (pinfunction "NC_2") (pintype "passive"))
    )
    (net (code "113") (name "unconnected-(U5-NC-Pad3)") (class "Default")
      (node (ref "U5") (pin "3") (pinfunction "NC_3") (pintype "passive"))
    )
    (net (code "114") (name "unconnected-(U5-NC-Pad4)") (class "Default")
      (node (ref "U5") (pin "4") (pinfunction "NC_4") (pintype "passive"))
    )
    (net (code "115") (name "unconnected-(U5-NC-Pad5)") (class "Default")
      (node (ref "U5") (pin "5") (pinfunction "NC_5") (pintype "passive"))
    )
    (net (code "116") (name "unconnected-(U5-NC-Pad6)") (class "Default")
      (node (ref "U5") (pin "6") (pinfunction "NC_6") (pintype "passive"))
    )
    (net (code "117") (name "unconnected-(U5-NC-Pad14)") (class "Default")
      (node (ref "U5") (pin "14") (pinfunction "NC_14") (pintype "passive"))
    )
    (net (code "118") (name "unconnected-(U5-NC-Pad15)") (class "Default")
      (node (ref "U5") (pin "15") (pinfunction "NC_15") (pintype "passive"))
    )
    (net (code "119") (name "unconnected-(U5-NC-Pad16)") (class "Default")
      (node (ref "U5") (pin "16") (pinfunction "NC_16") (pintype "passive"))
    )
    (net (code "120") (name "unconnected-(U5-NC-Pad17)") (class "Default")
      (node (ref "U5") (pin "17") (pinfunction "NC_17") (pintype "passive"))
    )
    (net (code "121") (name "unconnected-(U5-RESV-Pad19)") (class "Default")
      (node (ref "U5") (pin "19") (pinfunction "RESV_19") (pintype "passive"))
    )
    (net (code "122") (name "unconnected-(USB1-ID-Pad4)") (class "Default")
      (node (ref "USB1") (pin "4") (pinfunction "ID_4") (pintype "passive"))
    )
  )
)
